# BatteryManagement_neu.net
KiCad netlist of a schematic drawn in EAGLE
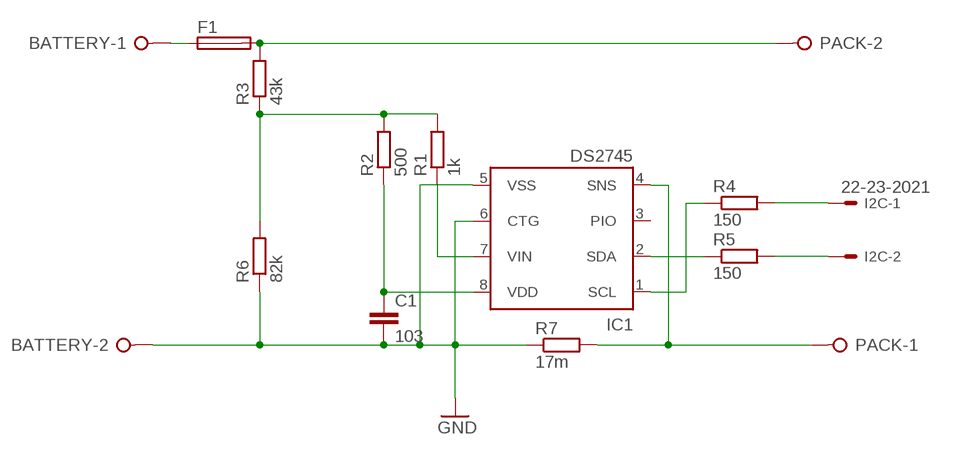
[diagram p0: schematic, sheet 1]

(export (version "E")
  (design (tool "Eeschema 10.0.6"))
  (components
    (comp (ref "BATTERY")
      (value "W237-02P")
      (footprint "eagle-import:W237-132")
      (libsource (lib "eagle-import") (part "W237-02P"))
    )
    (comp (ref "C1")
      (value "103")
      (footprint "eagle-import:C050-030X075")
      (libsource (lib "eagle-import") (part "C-EU050-030X075"))
    )
    (comp (ref "F1")
      (value "SH22,5")
      (footprint "eagle-import:SH22,5")
      (fields (field (name "MF") "SCHURTER") (field (name "MPN") "0031.8201"))
      (libsource (lib "eagle-import") (part "SH22,5"))
    )
    (comp (ref "I2C")
      (value "22-23-2021")
      (footprint "eagle-import:22-23-2021")
      (fields (field (name "MF") "MOLEX"))
      (libsource (lib "eagle-import") (part "22-23-2021"))
    )
    (comp (ref "IC1")
      (value "DS2745")
      (footprint "eagle-import:UMAX10")
      (libsource (lib "eagle-import") (part "DS2745"))
    )
    (comp (ref "PACK")
      (value "W237-02P")
      (footprint "eagle-import:W237-132")
      (libsource (lib "eagle-import") (part "W237-02P"))
    )
    (comp (ref "R1")
      (value "1k")
      (footprint "eagle-import:0207_10")
      (libsource (lib "eagle-import") (part "R-EU_0207/10"))
    )
    (comp (ref "R2")
      (value "500")
      (footprint "eagle-import:0207_10")
      (libsource (lib "eagle-import") (part "R-EU_0207/10"))
    )
    (comp (ref "R3")
      (value "43k")
      (footprint "eagle-import:0207_10")
      (libsource (lib "eagle-import") (part "R-EU_0207/10"))
    )
    (comp (ref "R4")
      (value "150")
      (footprint "eagle-import:0207_10")
      (libsource (lib "eagle-import") (part "R-EU_0207/10"))
    )
    (comp (ref "R5")
      (value "150")
      (footprint "eagle-import:0207_10")
      (libsource (lib "eagle-import") (part "R-EU_0207/10"))
    )
    (comp (ref "R6")
      (value "82k")
      (footprint "eagle-import:0207_10")
      (libsource (lib "eagle-import") (part "R-EU_0207/10"))
    )
    (comp (ref "R7")
      (value "17m")
      (footprint "eagle-import:R2010")
      (libsource (lib "eagle-import") (part "R-EU_R2010"))
    )
  )
  (nets
    (net (code "1") (name "GND") (class "Default")
      (node (ref "BATTERY") (pin "2") (pinfunction "KL_2") (pintype "passive"))
      (node (ref "C1") (pin "2") (pinfunction "2_2") (pintype "passive"))
      (node (ref "IC1") (pin "5") (pinfunction "VSS_5") (pintype "power_in"))
      (node (ref "IC1") (pin "6") (pinfunction "CTG_6") (pintype "power_in"))
      (node (ref "R6") (pin "1") (pinfunction "1_1") (pintype "passive"))
      (node (ref "R7") (pin "1") (pinfunction "1_1") (pintype "passive"))
    )
    (net (code "2") (name "Net-(BATTERYA-KL)") (class "Default")
      (node (ref "BATTERY") (pin "1") (pinfunction "KL_1") (pintype "passive"))
      (node (ref "F1") (pin "1") (pinfunction "1_1") (pintype "passive"))
    )
    (net (code "3") (name "Net-(I2CA-S)") (class "Default")
      (node (ref "I2C") (pin "1") (pinfunction "S_1") (pintype "passive"))
      (node (ref "R4") (pin "2") (pinfunction "2_2") (pintype "passive"))
    )
    (net (code "4") (name "Net-(I2CB-S)") (class "Default")
      (node (ref "I2C") (pin "2") (pinfunction "S_2") (pintype "passive"))
      (node (ref "R5") (pin "2") (pinfunction "2_2") (pintype "passive"))
    )
    (net (code "5") (name "Net-(IC1-SCL)") (class "Default")
      (node (ref "IC1") (pin "1") (pinfunction "SCL_1") (pintype "input"))
      (node (ref "R4") (pin "1") (pinfunction "1_1") (pintype "passive"))
    )
    (net (code "6") (name "Net-(IC1-SDA)") (class "Default")
      (node (ref "IC1") (pin "2") (pinfunction "SDA_2") (pintype "input"))
      (node (ref "R5") (pin "1") (pinfunction "1_1") (pintype "passive"))
    )
    (net (code "7") (name "Net-(IC1-SNS)") (class "Default")
      (node (ref "IC1") (pin "4") (pinfunction "SNS_4") (pintype "input"))
      (node (ref "PACK") (pin "1") (pinfunction "KL_1") (pintype "passive"))
      (node (ref "R7") (pin "2") (pinfunction "2_2") (pintype "passive"))
    )
    (net (code "8") (name "Net-(IC1-VDD)") (class "Default")
      (node (ref "C1") (pin "1") (pinfunction "1_1") (pintype "passive"))
      (node (ref "IC1") (pin "8") (pinfunction "VDD_8") (pintype "input"))
      (node (ref "R2") (pin "1") (pinfunction "1_1") (pintype "passive"))
    )
    (net (code "9") (name "Net-(IC1-VIN)") (class "Default")
      (node (ref "IC1") (pin "7") (pinfunction "VIN_7") (pintype "open_collector"))
      (node (ref "R1") (pin "1") (pinfunction "1_1") (pintype "passive"))
    )
    (net (code "10") (name "Net-(PACKB-KL)") (class "Default")
      (node (ref "F1") (pin "2") (pinfunction "2_2") (pintype "passive"))
      (node (ref "PACK") (pin "2") (pinfunction "KL_2") (pintype "passive"))
      (node (ref "R3") (pin "2") (pinfunction "2_2") (pintype "passive"))
    )
    (net (code "11") (name "Net-(R1-Pad2)") (class "Default")
      (node (ref "R1") (pin "2") (pinfunction "2_2") (pintype "passive"))
      (node (ref "R2") (pin "2") (pinfunction "2_2") (pintype "passive"))
      (node (ref "R3") (pin "1") (pinfunction "1_1") (pintype "passive"))
      (node (ref "R6") (pin "2") (pinfunction "2_2") (pintype "passive"))
    )
    (net (code "12") (name "unconnected-(IC1-PIO-Pad3)") (class "Default")
      (node (ref "IC1") (pin "3") (pinfunction "PIO_3") (pintype "input"))
    )
  )
)
